# Servo.net
KiCad netlist of a schematic drawn in EAGLE
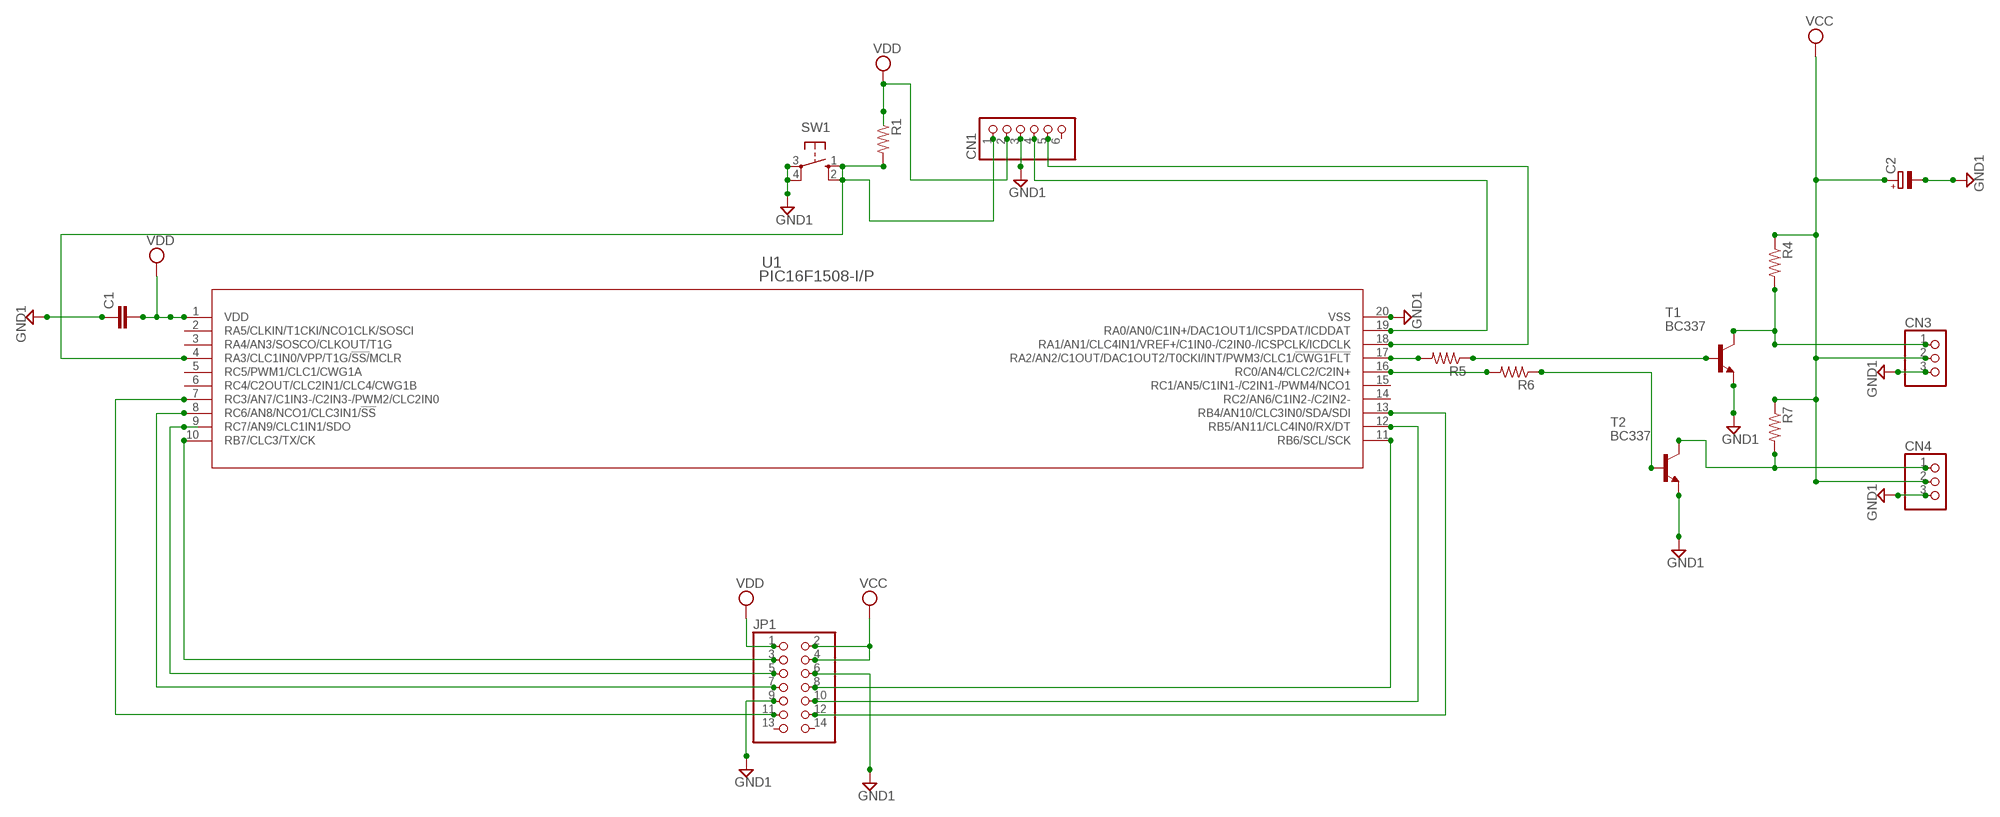
[diagram p0: schematic, sheet 1]

(export (version "E")
  (design (tool "Eeschema 10.0.6"))
  (components
    (comp (ref "C1")
      (value "C-EU025-025X050")
      (footprint "eagle-import:C025-025X050")
      (libsource (lib "eagle-import") (part "C-EU025-025X050"))
    )
    (comp (ref "C2")
      (value "CPOL-EUA")
      (footprint "eagle-import:PANASONIC_A")
      (libsource (lib "eagle-import") (part "CPOL-EUA"))
    )
    (comp (ref "CN1")
      (value "PINHD-1X6")
      (footprint "eagle-import:1X06")
      (libsource (lib "eagle-import") (part "PINHD-1X6"))
    )
    (comp (ref "CN3")
      (value "PINHD-1X3")
      (footprint "eagle-import:1X03")
      (libsource (lib "eagle-import") (part "PINHD-1X3"))
    )
    (comp (ref "CN4")
      (value "PINHD-1X3")
      (footprint "eagle-import:1X03")
      (libsource (lib "eagle-import") (part "PINHD-1X3"))
    )
    (comp (ref "JP1")
      (value "PINHD-2X7")
      (footprint "eagle-import:2X07")
      (libsource (lib "eagle-import") (part "PINHD-2X7"))
    )
    (comp (ref "R1")
      (value "R-US_R0603")
      (footprint "eagle-import:R0603")
      (libsource (lib "eagle-import") (part "R-US_R0603"))
    )
    (comp (ref "R4")
      (value "R-US_R0603")
      (footprint "eagle-import:R0603")
      (libsource (lib "eagle-import") (part "R-US_R0603"))
    )
    (comp (ref "R5")
      (value "R-US_R0603")
      (footprint "eagle-import:R0603")
      (libsource (lib "eagle-import") (part "R-US_R0603"))
    )
    (comp (ref "R6")
      (value "R-US_R0603")
      (footprint "eagle-import:R0603")
      (libsource (lib "eagle-import") (part "R-US_R0603"))
    )
    (comp (ref "R7")
      (value "R-US_R0603")
      (footprint "eagle-import:R0603")
      (libsource (lib "eagle-import") (part "R-US_R0603"))
    )
    (comp (ref "SW1")
      (value "10-XX")
      (footprint "eagle-import:B3F-10XX")
      (fields (field (name "MPN") "B3F-1000"))
      (libsource (lib "eagle-import") (part "10-XX"))
    )
    (comp (ref "T1")
      (value "BC337")
      (footprint "eagle-import:TO92")
      (libsource (lib "eagle-import") (part "BC337"))
    )
    (comp (ref "T2")
      (value "BC337")
      (footprint "eagle-import:TO92")
      (libsource (lib "eagle-import") (part "BC337"))
    )
    (comp (ref "U1")
      (value "PIC16F1508-I/P")
      (footprint "eagle-import:PDIP20_300MC")
      (fields (field (name "MANUFACTURER_PART_NUMBER") "pic16f1508ip"))
      (libsource (lib "eagle-import") (part "PIC16F1508-I/P"))
    )
  )
  (nets
    (net (code "1") (name "GND1") (class "Default")
      (node (ref "C1") (pin "1") (pinfunction "1_1") (pintype "passive"))
      (node (ref "C2") (pin "-") (pinfunction "-_-") (pintype "passive"))
      (node (ref "CN1") (pin "3") (pinfunction "3_3") (pintype "passive"))
      (node (ref "CN3") (pin "3") (pinfunction "3_3") (pintype "passive"))
      (node (ref "CN4") (pin "3") (pinfunction "3_3") (pintype "passive"))
      (node (ref "JP1") (pin "6") (pinfunction "6_6") (pintype "passive"))
      (node (ref "JP1") (pin "9") (pinfunction "9_9") (pintype "passive"))
      (node (ref "SW1") (pin "3") (pinfunction "P_3") (pintype "passive"))
      (node (ref "SW1") (pin "4") (pinfunction "P1_4") (pintype "passive"))
      (node (ref "T1") (pin "1") (pinfunction "E_1") (pintype "passive"))
      (node (ref "T2") (pin "1") (pinfunction "E_1") (pintype "passive"))
      (node (ref "U1") (pin "20") (pinfunction "VSS_20") (pintype "power_in"))
    )
    (net (code "2") (name "Net-(SW1-S)") (class "Default")
      (node (ref "CN1") (pin "1") (pinfunction "1_1") (pintype "passive"))
      (node (ref "R1") (pin "2") (pinfunction "2_2") (pintype "passive"))
      (node (ref "SW1") (pin "1") (pinfunction "S_1") (pintype "passive"))
      (node (ref "SW1") (pin "2") (pinfunction "S1_2") (pintype "passive"))
      (node (ref "U1") (pin "4") (pinfunction "RA3/CLC1IN0/VPP/T1G/~{SS/}MCLR_4") (pintype "bidirectional"))
    )
    (net (code "3") (name "Net-(T1-B)") (class "Default")
      (node (ref "R5") (pin "1") (pinfunction "1_1") (pintype "passive"))
      (node (ref "T1") (pin "2") (pinfunction "B_2") (pintype "passive"))
    )
    (net (code "4") (name "Net-(T1-C)") (class "Default")
      (node (ref "CN3") (pin "1") (pinfunction "1_1") (pintype "passive"))
      (node (ref "R4") (pin "2") (pinfunction "2_2") (pintype "passive"))
      (node (ref "T1") (pin "3") (pinfunction "C_3") (pintype "passive"))
    )
    (net (code "5") (name "Net-(T2-B)") (class "Default")
      (node (ref "R6") (pin "1") (pinfunction "1_1") (pintype "passive"))
      (node (ref "T2") (pin "2") (pinfunction "B_2") (pintype "passive"))
    )
    (net (code "6") (name "Net-(T2-C)") (class "Default")
      (node (ref "CN4") (pin "1") (pinfunction "1_1") (pintype "passive"))
      (node (ref "R7") (pin "2") (pinfunction "2_2") (pintype "passive"))
      (node (ref "T2") (pin "3") (pinfunction "C_3") (pintype "passive"))
    )
    (net (code "7") (name "Net-(U1-RA0{slash}AN0{slash}C1IN+{slash}DAC1OUT1{slash}ICSPDAT{slash}ICDDAT)") (class "Default")
      (node (ref "CN1") (pin "4") (pinfunction "4_4") (pintype "passive"))
      (node (ref "U1") (pin "19") (pinfunction "RA0/AN0/C1IN+/DAC1OUT1/ICSPDAT/ICDDAT_19") (pintype "bidirectional"))
    )
    (net (code "8") (name "Net-(U1-RA1{slash}AN1{slash}CLC4IN1{slash}VREF+{slash}C1IN0-{slash}C2IN0-{slash}ICSPCLK{slash}ICDCLK)") (class "Default")
      (node (ref "CN1") (pin "5") (pinfunction "5_5") (pintype "passive"))
      (node (ref "U1") (pin "18") (pinfunction "RA1/AN1/CLC4IN1/VREF+/C1IN0-/C2IN0-/ICSPCLK/ICDCLK_18") (pintype "bidirectional"))
    )
    (net (code "9") (name "Net-(U1-RA2{slash}AN2{slash}C1OUT{slash}DAC1OUT2{slash}T0CKI{slash}INT{slash}PWM3{slash}CLC1{slash}~{CWG1FLT})") (class "Default")
      (node (ref "R5") (pin "2") (pinfunction "2_2") (pintype "passive"))
      (node (ref "U1") (pin "17") (pinfunction "RA2/AN2/C1OUT/DAC1OUT2/T0CKI/INT/PWM3/CLC1/~{CWG1FLT}_17") (pintype "bidirectional"))
    )
    (net (code "10") (name "Net-(U1-RB4{slash}AN10{slash}CLC3IN0{slash}SDA{slash}SDI)") (class "Default")
      (node (ref "JP1") (pin "12") (pinfunction "12_12") (pintype "passive"))
      (node (ref "U1") (pin "13") (pinfunction "RB4/AN10/CLC3IN0/SDA/SDI_13") (pintype "bidirectional"))
    )
    (net (code "11") (name "Net-(U1-RB5{slash}AN11{slash}CLC4IN0{slash}RX{slash}DT)") (class "Default")
      (node (ref "JP1") (pin "10") (pinfunction "10_10") (pintype "passive"))
      (node (ref "U1") (pin "12") (pinfunction "RB5/AN11/CLC4IN0/RX/DT_12") (pintype "bidirectional"))
    )
    (net (code "12") (name "Net-(U1-RB6{slash}SCL{slash}SCK)") (class "Default")
      (node (ref "JP1") (pin "8") (pinfunction "8_8") (pintype "passive"))
      (node (ref "U1") (pin "11") (pinfunction "RB6/SCL/SCK_11") (pintype "bidirectional"))
    )
    (net (code "13") (name "Net-(U1-RB7{slash}CLC3{slash}TX{slash}CK)") (class "Default")
      (node (ref "JP1") (pin "3") (pinfunction "3_3") (pintype "passive"))
      (node (ref "U1") (pin "10") (pinfunction "RB7/CLC3/TX/CK_10") (pintype "bidirectional"))
    )
    (net (code "14") (name "Net-(U1-RC0{slash}AN4{slash}CLC2{slash}C2IN+)") (class "Default")
      (node (ref "R6") (pin "2") (pinfunction "2_2") (pintype "passive"))
      (node (ref "U1") (pin "16") (pinfunction "RC0/AN4/CLC2/C2IN+_16") (pintype "bidirectional"))
    )
    (net (code "15") (name "Net-(U1-RC3{slash}AN7{slash}C1IN3-{slash}C2IN3-{slash}PWM2{slash}CLC2IN0)") (class "Default")
      (node (ref "JP1") (pin "11") (pinfunction "11_11") (pintype "passive"))
      (node (ref "U1") (pin "7") (pinfunction "RC3/AN7/C1IN3-/C2IN3-/PWM2/CLC2IN0_7") (pintype "bidirectional"))
    )
    (net (code "16") (name "Net-(U1-RC6{slash}AN8{slash}NCO1{slash}CLC3IN1{slash}~{SS})") (class "Default")
      (node (ref "JP1") (pin "7") (pinfunction "7_7") (pintype "passive"))
      (node (ref "U1") (pin "8") (pinfunction "RC6/AN8/NCO1/CLC3IN1/~{SS}_8") (pintype "bidirectional"))
    )
    (net (code "17") (name "Net-(U1-RC7{slash}AN9{slash}CLC1IN1{slash}SDO)") (class "Default")
      (node (ref "JP1") (pin "5") (pinfunction "5_5") (pintype "passive"))
      (node (ref "U1") (pin "9") (pinfunction "RC7/AN9/CLC1IN1/SDO_9") (pintype "bidirectional"))
    )
    (net (code "18") (name "VCC") (class "Default")
      (node (ref "C2") (pin "+") (pinfunction "+_+") (pintype "passive"))
      (node (ref "CN3") (pin "2") (pinfunction "2_2") (pintype "passive"))
      (node (ref "CN4") (pin "2") (pinfunction "2_2") (pintype "passive"))
      (node (ref "JP1") (pin "2") (pinfunction "2_2") (pintype "passive"))
      (node (ref "JP1") (pin "4") (pinfunction "4_4") (pintype "passive"))
      (node (ref "R4") (pin "1") (pinfunction "1_1") (pintype "passive"))
      (node (ref "R7") (pin "1") (pinfunction "1_1") (pintype "passive"))
    )
    (net (code "19") (name "VDD") (class "Default")
      (node (ref "C1") (pin "2") (pinfunction "2_2") (pintype "passive"))
      (node (ref "CN1") (pin "2") (pinfunction "2_2") (pintype "passive"))
      (node (ref "JP1") (pin "1") (pinfunction "1_1") (pintype "passive"))
      (node (ref "R1") (pin "1") (pinfunction "1_1") (pintype "passive"))
      (node (ref "U1") (pin "1") (pinfunction "VDD_1") (pintype "power_in"))
    )
    (net (code "20") (name "unconnected-(CN1-Pad6)") (class "Default")
      (node (ref "CN1") (pin "6") (pinfunction "6_6") (pintype "passive"))
    )
    (net (code "21") (name "unconnected-(JP1-Pad13)") (class "Default")
      (node (ref "JP1") (pin "13") (pinfunction "13_13") (pintype "passive"))
    )
    (net (code "22") (name "unconnected-(JP1-Pad14)") (class "Default")
      (node (ref "JP1") (pin "14") (pinfunction "14_14") (pintype "passive"))
    )
    (net (code "23") (name "unconnected-(U1-RA4{slash}AN3{slash}SOSCO{slash}CLKOUT{slash}T1G-Pad3)") (class "Default")
      (node (ref "U1") (pin "3") (pinfunction "RA4/AN3/SOSCO/CLKOUT/T1G_3") (pintype "bidirectional"))
    )
    (net (code "24") (name "unconnected-(U1-RA5{slash}CLKIN{slash}T1CKI{slash}NCO1CLK{slash}SOSCI-Pad2)") (class "Default")
      (node (ref "U1") (pin "2") (pinfunction "RA5/CLKIN/T1CKI/NCO1CLK/SOSCI_2") (pintype "bidirectional"))
    )
    (net (code "25") (name "unconnected-(U1-RC1{slash}AN5{slash}C1IN1-{slash}C2IN1-{slash}PWM4{slash}NCO1-Pad15)") (class "Default")
      (node (ref "U1") (pin "15") (pinfunction "RC1/AN5/C1IN1-/C2IN1-/PWM4/NCO1_15") (pintype "bidirectional"))
    )
    (net (code "26") (name "unconnected-(U1-RC2{slash}AN6{slash}C1IN2-{slash}C2IN2--Pad14)") (class "Default")
      (node (ref "U1") (pin "14") (pinfunction "RC2/AN6/C1IN2-/C2IN2-_14") (pintype "bidirectional"))
    )
    (net (code "27") (name "unconnected-(U1-RC4{slash}C2OUT{slash}CLC2IN1{slash}CLC4{slash}CWG1B-Pad6)") (class "Default")
      (node (ref "U1") (pin "6") (pinfunction "RC4/C2OUT/CLC2IN1/CLC4/CWG1B_6") (pintype "bidirectional"))
    )
    (net (code "28") (name "unconnected-(U1-RC5{slash}PWM1{slash}CLC1{slash}CWG1A-Pad5)") (class "Default")
      (node (ref "U1") (pin "5") (pinfunction "RC5/PWM1/CLC1/CWG1A_5") (pintype "bidirectional"))
    )
  )
)
